# L-D5019-05-03.net
KiCad netlist of a schematic drawn in Altium Designer
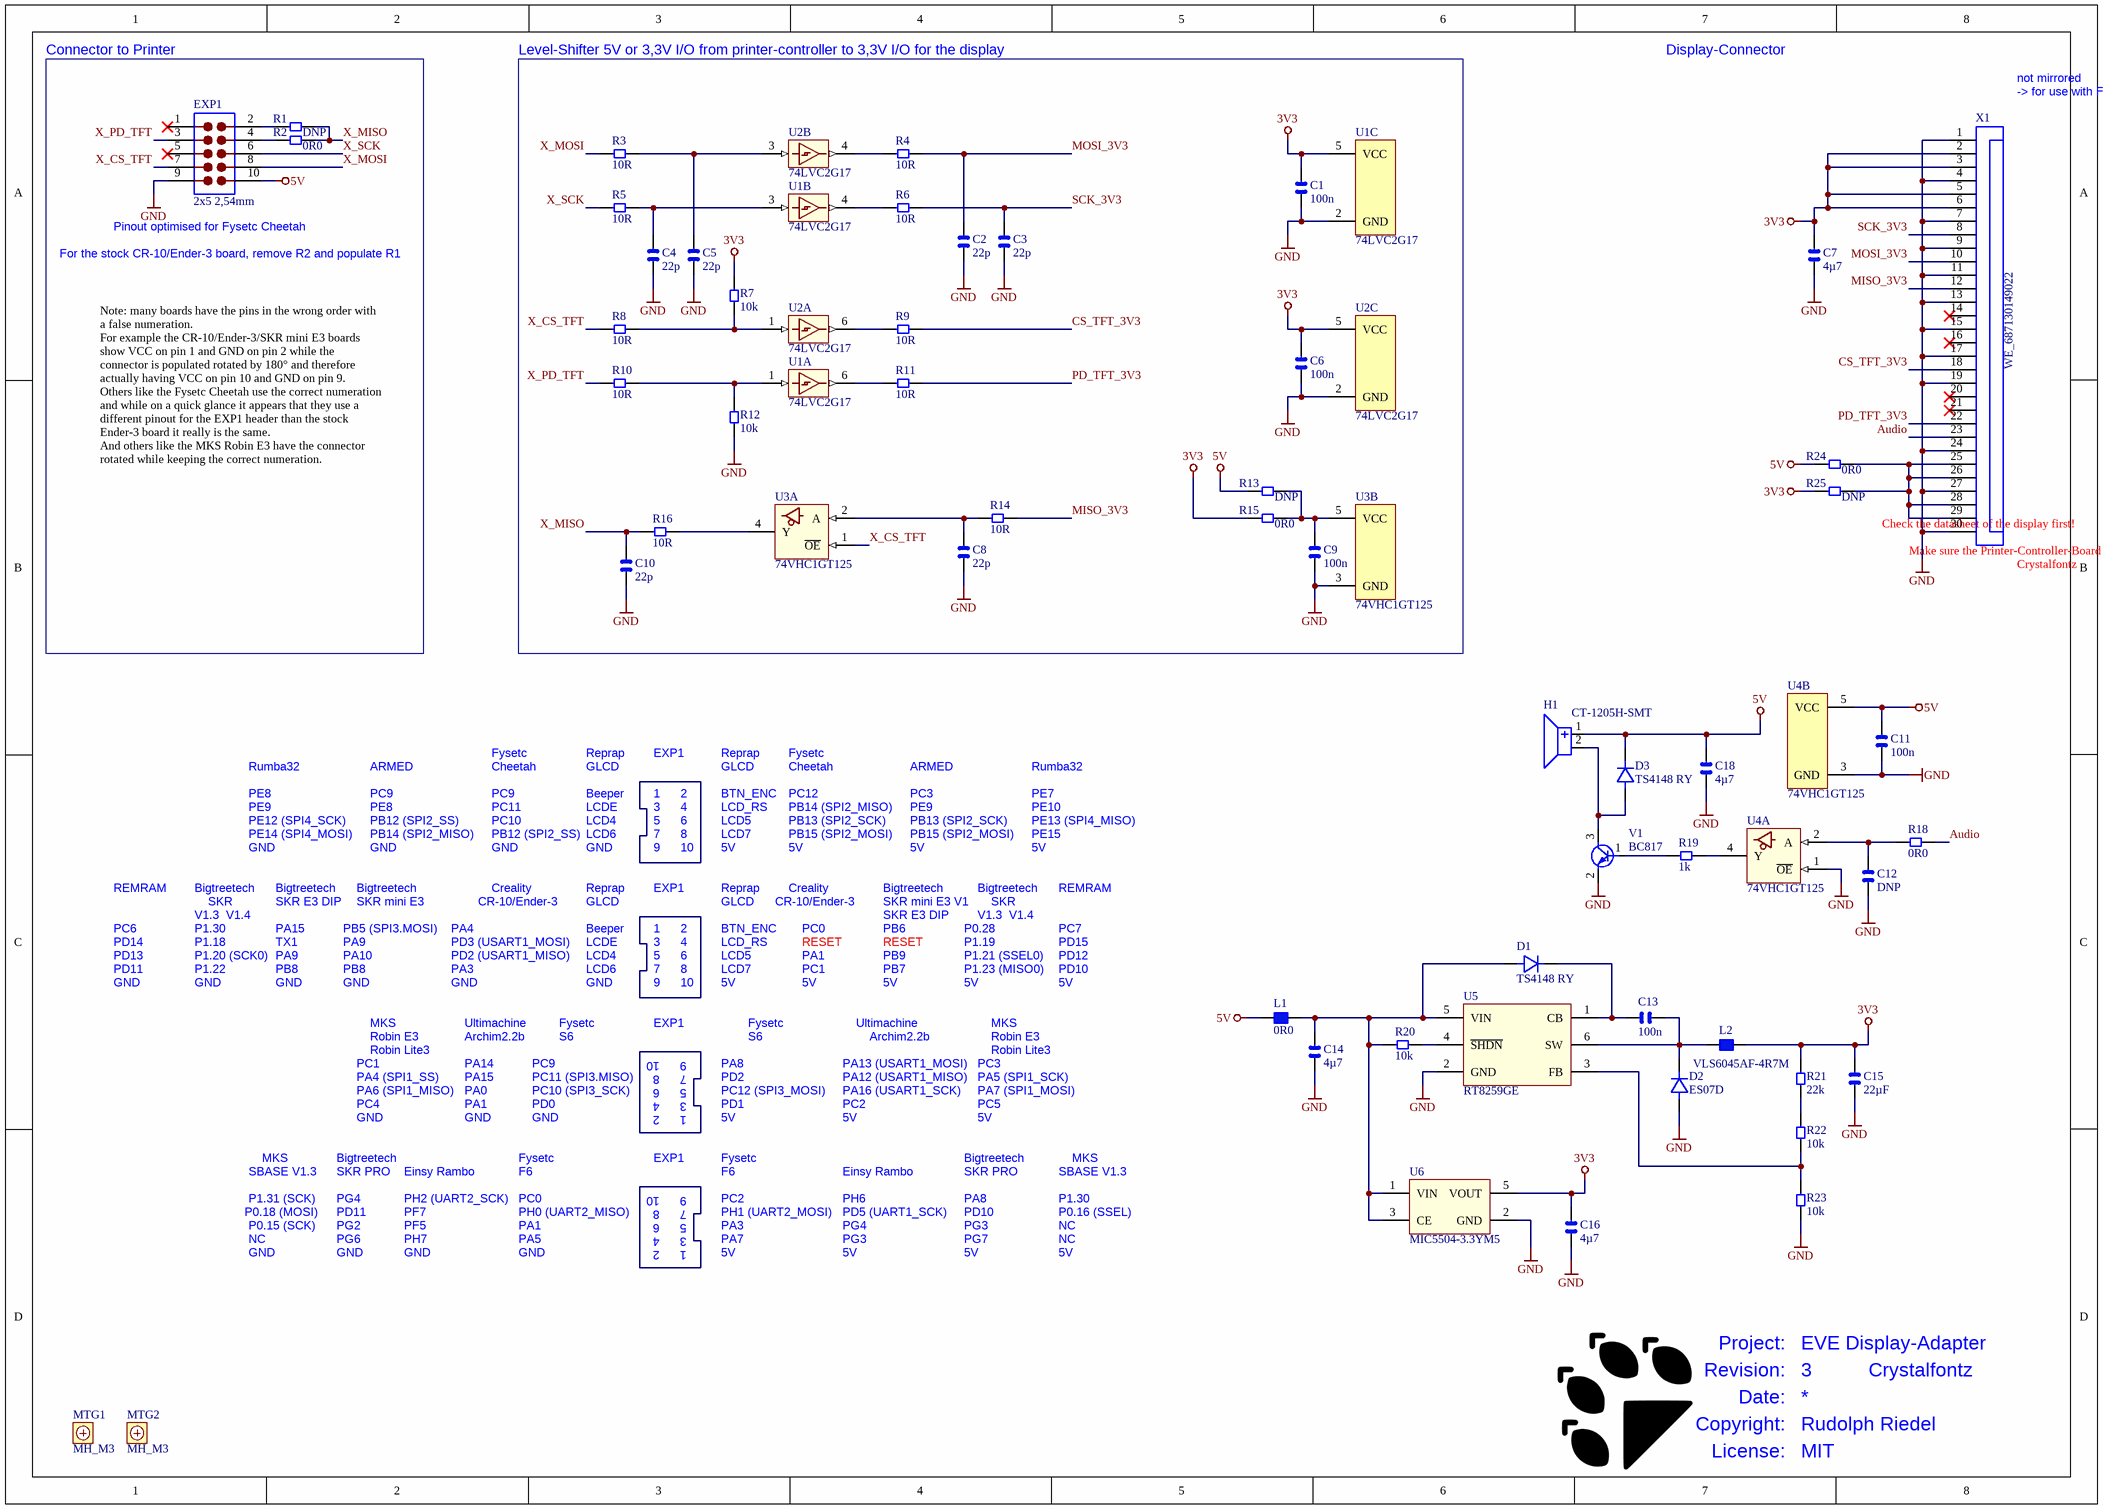
[diagram p0: L-D5019-05-03.SchDoc]

(export (version "E")
  (design (tool "Eeschema 10.0.6"))
  (components
    (comp (ref "C1")
      (value "100n")
      (footprint "CAPC2012X14L")
      (description "0805 Chip Capacitor")
      (fields (field (name "PART NUMBER") "CAPC_0805") (field (name "EDITOR") "rriedel"))
      (libsource (lib "HW-Labor_GF") (part "CAP_2_V2"))
    )
    (comp (ref "C2")
      (value "22p")
      (footprint "CAPC2012X14L")
      (description "0805 Chip Capacitor")
      (fields (field (name "PART NUMBER") "CAPC_0805") (field (name "EDITOR") "rriedel"))
      (libsource (lib "HW-Labor_GF") (part "CAP_2_V2"))
    )
    (comp (ref "C3")
      (value "22p")
      (footprint "CAPC2012X14L")
      (description "0805 Chip Capacitor")
      (fields (field (name "PART NUMBER") "CAPC_0805") (field (name "EDITOR") "rriedel"))
      (libsource (lib "HW-Labor_GF") (part "CAP_2_V2"))
    )
    (comp (ref "C4")
      (value "22p")
      (footprint "CAPC2012X14L")
      (description "0805 Chip Capacitor")
      (fields (field (name "PART NUMBER") "CAPC_0805") (field (name "EDITOR") "rriedel"))
      (libsource (lib "HW-Labor_GF") (part "CAP_2_V2"))
    )
    (comp (ref "C5")
      (value "22p")
      (footprint "CAPC2012X14L")
      (description "0805 Chip Capacitor")
      (fields (field (name "PART NUMBER") "CAPC_0805") (field (name "EDITOR") "rriedel"))
      (libsource (lib "HW-Labor_GF") (part "CAP_2_V2"))
    )
    (comp (ref "C6")
      (value "100n")
      (footprint "CAPC2012X14L")
      (description "0805 Chip Capacitor")
      (fields (field (name "PART NUMBER") "CAPC_0805") (field (name "EDITOR") "rriedel"))
      (libsource (lib "HW-Labor_GF") (part "CAP_2_V2"))
    )
    (comp (ref "C7")
      (value "4µ7")
      (footprint "CAPC2012X14L")
      (description "0805 Chip Capacitor")
      (fields (field (name "PART NUMBER") "CAPC_0805") (field (name "EDITOR") "rriedel"))
      (libsource (lib "HW-Labor_GF") (part "CAP_2_V2"))
    )
    (comp (ref "C8")
      (value "22p")
      (footprint "CAPC2012X14L")
      (description "0805 Chip Capacitor")
      (fields (field (name "PART NUMBER") "CAPC_0805") (field (name "EDITOR") "rriedel"))
      (libsource (lib "HW-Labor_GF") (part "CAP_2_V2"))
    )
    (comp (ref "C9")
      (value "100n")
      (footprint "CAPC2012X14L")
      (description "0805 Chip Capacitor")
      (fields (field (name "PART NUMBER") "CAPC_0805") (field (name "EDITOR") "rriedel"))
      (libsource (lib "HW-Labor_GF") (part "CAP_2_V2"))
    )
    (comp (ref "C10")
      (value "22p")
      (footprint "CAPC2012X14L")
      (description "0805 Chip Capacitor")
      (fields (field (name "PART NUMBER") "CAPC_0805") (field (name "EDITOR") "rriedel"))
      (libsource (lib "HW-Labor_GF") (part "CAP_2_V2"))
    )
    (comp (ref "C11")
      (value "100n")
      (footprint "CAPC2012X14L")
      (description "0805 Chip Capacitor")
      (fields (field (name "PART NUMBER") "CAPC_0805") (field (name "EDITOR") "rriedel"))
      (libsource (lib "HW-Labor_GF") (part "CAP_2_V2"))
    )
    (comp (ref "C12")
      (value "DNP")
      (footprint "CAPC2012X14L")
      (description "0805 Chip Capacitor")
      (fields (field (name "PART NUMBER") "CAPC_0805") (field (name "EDITOR") "rriedel"))
      (libsource (lib "HW-Labor_GF") (part "CAP_2_V2"))
    )
    (comp (ref "C13")
      (value "100n")
      (footprint "CAPC2012X14L")
      (description "0805 Chip Capacitor")
      (fields (field (name "PART NUMBER") "CAPC_0805") (field (name "EDITOR") "rriedel"))
      (libsource (lib "HW-Labor_GF") (part "CAP_2_V2"))
    )
    (comp (ref "C14")
      (value "4µ7")
      (footprint "CAPC2012X14L")
      (description "0805 Chip Capacitor")
      (fields (field (name "PART NUMBER") "CAPC_0805") (field (name "EDITOR") "rriedel"))
      (libsource (lib "HW-Labor_GF") (part "CAP_2_V2"))
    )
    (comp (ref "C15")
      (value "22µF")
      (footprint "CAPC3216X19N")
      (description "1206 Chip Capacitor")
      (fields (field (name "PART NUMBER") "CAPC_1206") (field (name "EDITOR") "rriedel"))
      (libsource (lib "HW-Labor_GF") (part "CAP_2_V2"))
    )
    (comp (ref "C16")
      (value "4µ7")
      (footprint "CAPC2012X14L")
      (description "0805 Chip Capacitor")
      (fields (field (name "PART NUMBER") "CAPC_0805") (field (name "ERSTELLER") "rriedel"))
      (libsource (lib "HW-Labor_GF") (part "CAP_2_V2"))
    )
    (comp (ref "C18")
      (value "4µ7")
      (footprint "CAPC2012X14L")
      (description "0805 Chip Capacitor")
      (fields (field (name "PART NUMBER") "CAPC_0805") (field (name "ERSTELLER") "rriedel"))
      (libsource (lib "HW-Labor_GF") (part "CAP_2_V2"))
    )
    (comp (ref "D1")
      (value "TS4148 RY")
      (footprint "DIOC2012X10N")
      (description "Small Signal Diode IF 0.3A, VR 75V, 0805")
      (fields
        (field (name "PART NUMBER") "TSC_TS4148 RY")
        (field (name "MANUFACTURER") "TSC")
        (field (name "EDITOR") "rriedel")
      )
      (libsource (lib "HW-Labor_GF") (part "Diode_A2_K1"))
    )
    (comp (ref "D2")
      (value "ES07D")
      (footprint "DIOM2818X11N")
      (description "Ultrafast Rectifier Surface Mount,  IF 0.5A, VR 100V, DO-219AB, AEC-Q101")
      (fields (field (name "MANUFACTURER") "Vishay") (field (name "EDITOR") "rriedel"))
      (libsource (lib "HW-Labor_GF") (part "Diode_A2_K1"))
    )
    (comp (ref "D3")
      (value "TS4148 RY")
      (footprint "DIOC2012X10N")
      (description "Small Signal Diode IF 0.3A, VR 75V, 0805")
      (fields
        (field (name "PART NUMBER") "TSC_TS4148 RY")
        (field (name "MANUFACTURER") "TSC")
        (field (name "EDITOR") "rriedel")
      )
      (libsource (lib "HW-Labor_GF") (part "Diode_A2_K1"))
    )
    (comp (ref "EXP1")
      (value "2x5 2,54mm")
      (footprint "PINH_2x5_2_54mm_shroud")
      (description "Pin-Header 2,54 mm 2x5pins, shrouded")
      (fields (field (name "PART NUMBER") "PINH_2x5_2_54") (field (name "EDITOR") "rriedel"))
      (libsource (lib "HW-Labor_GF") (part "CONM_2x5_V2"))
    )
    (comp (ref "H1")
      (value "CT-1205H-SMT")
      (footprint "CT-1205H-SMT")
      (description "Speaker, Magnetic, 47R, 60mA, 88dBA, SMT, 12.8 x 12.8 mm,  height 10 mm")
      (fields
        (field (name "MANUFACTURER") "CUI")
        (field (name "DISTRIBUTOR_1_PART_NUMBER") "102-1266-1-ND")
        (field (name "EDITOR") "rriedel")
      )
      (libsource (lib "HW-Labor_GF") (part "Speaker"))
    )
    (comp (ref "L1")
      (value "0R0")
      (footprint "INDC2012X10L")
      (description "0805 Chip Inductor")
      (fields (field (name "PART NUMBER") "INDC_0805") (field (name "EDITOR") "rriedel"))
      (libsource (lib "HW-Labor_GF") (part "IND_2_V1"))
    )
    (comp (ref "L2")
      (value "VLS6045AF-4R7M")
      (footprint "PowerInductor_6x6")
      (description "4,7µH, shielded, 4,7A, 26mR")
      (fields
        (field (name "MANUFACTURER") "TDK")
        (field (name "DISTRIBUTOR_1_PART_NUMBER") "445-180835-1-ND")
        (field (name "EDITOR") "rriedel")
      )
      (libsource (lib "HW-Labor_GF") (part "IND_2_V1"))
    )
    (comp (ref "MTG1")
      (value "MH_M3")
      (footprint "HOLE_3_2MM")
      (description "Mounting-Hole for M3 screws")
      (fields (field (name "EDITOR") "rriedel"))
      (libsource (lib "HW-Labor_GF") (part "MTG_V1"))
    )
    (comp (ref "MTG2")
      (value "MH_M3")
      (footprint "HOLE_3_2MM")
      (description "Mounting-Hole for M3 screws")
      (fields (field (name "EDITOR") "rriedel"))
      (libsource (lib "HW-Labor_GF") (part "MTG_V1"))
    )
    (comp (ref "R1")
      (value "DNP")
      (footprint "RESC2012X06L")
      (description "0805 Chip Resistor")
      (fields (field (name "PART NUMBER") "RESC_0805") (field (name "EDITOR") "rriedel"))
      (libsource (lib "HW-Labor_GF") (part "RES_2_V2"))
    )
    (comp (ref "R2")
      (value "0R0")
      (footprint "RESC2012X06L")
      (description "0805 Chip Resistor")
      (fields (field (name "PART NUMBER") "RESC_0805") (field (name "EDITOR") "rriedel"))
      (libsource (lib "HW-Labor_GF") (part "RES_2_V2"))
    )
    (comp (ref "R3")
      (value "10R")
      (footprint "RESC2012X06L")
      (description "0805 Chip Resistor")
      (fields (field (name "PART NUMBER") "RESC_0805") (field (name "EDITOR") "rriedel"))
      (libsource (lib "HW-Labor_GF") (part "RES_2_V2"))
    )
    (comp (ref "R4")
      (value "10R")
      (footprint "RESC2012X06L")
      (description "0805 Chip Resistor")
      (fields (field (name "PART NUMBER") "RESC_0805") (field (name "EDITOR") "rriedel"))
      (libsource (lib "HW-Labor_GF") (part "RES_2_V2"))
    )
    (comp (ref "R5")
      (value "10R")
      (footprint "RESC2012X06L")
      (description "0805 Chip Resistor")
      (fields (field (name "PART NUMBER") "RESC_0805") (field (name "EDITOR") "rriedel"))
      (libsource (lib "HW-Labor_GF") (part "RES_2_V2"))
    )
    (comp (ref "R6")
      (value "10R")
      (footprint "RESC2012X06L")
      (description "0805 Chip Resistor")
      (fields (field (name "PART NUMBER") "RESC_0805") (field (name "EDITOR") "rriedel"))
      (libsource (lib "HW-Labor_GF") (part "RES_2_V2"))
    )
    (comp (ref "R7")
      (value "10k")
      (footprint "RESC2012X06L")
      (description "0805 Chip Resistor")
      (fields (field (name "PART NUMBER") "RESC_0805") (field (name "EDITOR") "rriedel"))
      (libsource (lib "HW-Labor_GF") (part "RES_2_V2"))
    )
    (comp (ref "R8")
      (value "10R")
      (footprint "RESC2012X06L")
      (description "0805 Chip Resistor")
      (fields (field (name "PART NUMBER") "RESC_0805") (field (name "EDITOR") "rriedel"))
      (libsource (lib "HW-Labor_GF") (part "RES_2_V2"))
    )
    (comp (ref "R9")
      (value "10R")
      (footprint "RESC2012X06L")
      (description "0805 Chip Resistor")
      (fields (field (name "PART NUMBER") "RESC_0805") (field (name "EDITOR") "rriedel"))
      (libsource (lib "HW-Labor_GF") (part "RES_2_V2"))
    )
    (comp (ref "R10")
      (value "10R")
      (footprint "RESC2012X06L")
      (description "0805 Chip Resistor")
      (fields (field (name "PART NUMBER") "RESC_0805") (field (name "EDITOR") "rriedel"))
      (libsource (lib "HW-Labor_GF") (part "RES_2_V2"))
    )
    (comp (ref "R11")
      (value "10R")
      (footprint "RESC2012X06L")
      (description "0805 Chip Resistor")
      (fields (field (name "PART NUMBER") "RESC_0805") (field (name "EDITOR") "rriedel"))
      (libsource (lib "HW-Labor_GF") (part "RES_2_V2"))
    )
    (comp (ref "R12")
      (value "10k")
      (footprint "RESC2012X06L")
      (description "0805 Chip Resistor")
      (fields (field (name "PART NUMBER") "RESC_0805") (field (name "EDITOR") "rriedel"))
      (libsource (lib "HW-Labor_GF") (part "RES_2_V2"))
    )
    (comp (ref "R13")
      (value "DNP")
      (footprint "RESC2012X06L")
      (description "0805 Chip Resistor")
      (fields (field (name "PART NUMBER") "RESC_0805") (field (name "EDITOR") "rriedel"))
      (libsource (lib "HW-Labor_GF") (part "RES_2_V2"))
    )
    (comp (ref "R14")
      (value "10R")
      (footprint "RESC2012X06L")
      (description "0805 Chip Resistor")
      (fields (field (name "PART NUMBER") "RESC_0805") (field (name "EDITOR") "rriedel"))
      (libsource (lib "HW-Labor_GF") (part "RES_2_V2"))
    )
    (comp (ref "R15")
      (value "0R0")
      (footprint "RESC2012X06L")
      (description "0805 Chip Resistor")
      (fields (field (name "PART NUMBER") "RESC_0805") (field (name "EDITOR") "rriedel"))
      (libsource (lib "HW-Labor_GF") (part "RES_2_V2"))
    )
    (comp (ref "R16")
      (value "10R")
      (footprint "RESC2012X06L")
      (description "0805 Chip Resistor")
      (fields (field (name "PART NUMBER") "RESC_0805") (field (name "EDITOR") "rriedel"))
      (libsource (lib "HW-Labor_GF") (part "RES_2_V2"))
    )
    (comp (ref "R18")
      (value "0R0")
      (footprint "RESC2012X06L")
      (description "0805 Chip Resistor")
      (fields (field (name "PART NUMBER") "RESC_0805") (field (name "EDITOR") "rriedel"))
      (libsource (lib "HW-Labor_GF") (part "RES_2_V2"))
    )
    (comp (ref "R19")
      (value "1k")
      (footprint "RESC2012X06L")
      (description "0805 Chip Resistor")
      (fields (field (name "PART NUMBER") "RESC_0805") (field (name "EDITOR") "rriedel"))
      (libsource (lib "HW-Labor_GF") (part "RES_2_V2"))
    )
    (comp (ref "R20")
      (value "10k")
      (footprint "RESC2012X06L")
      (description "0805 Chip Resistor")
      (fields (field (name "PART NUMBER") "RESC_0805") (field (name "EDITOR") "rriedel"))
      (libsource (lib "HW-Labor_GF") (part "RES_2_V2"))
    )
    (comp (ref "R21")
      (value "22k")
      (footprint "RESC2012X06L")
      (description "0805 Chip Resistor")
      (fields (field (name "PART NUMBER") "RESC_0805") (field (name "EDITOR") "rriedel"))
      (libsource (lib "HW-Labor_GF") (part "RES_2_V2"))
    )
    (comp (ref "R22")
      (value "10k")
      (footprint "RESC2012X06L")
      (description "0805 Chip Resistor")
      (fields (field (name "PART NUMBER") "RESC_0805") (field (name "EDITOR") "rriedel"))
      (libsource (lib "HW-Labor_GF") (part "RES_2_V2"))
    )
    (comp (ref "R23")
      (value "10k")
      (footprint "RESC2012X06L")
      (description "0805 Chip Resistor")
      (fields (field (name "PART NUMBER") "RESC_0805") (field (name "EDITOR") "rriedel"))
      (libsource (lib "HW-Labor_GF") (part "RES_2_V2"))
    )
    (comp (ref "R24")
      (value "0R0")
      (footprint "RESC2012X06L")
      (description "0805 Chip Resistor")
      (fields (field (name "PART NUMBER") "RESC_0805") (field (name "EDITOR") "rriedel"))
      (libsource (lib "HW-Labor_GF") (part "RES_2_V2"))
    )
    (comp (ref "R25")
      (value "DNP")
      (footprint "RESC2012X06L")
      (description "0805 Chip Resistor")
      (fields (field (name "PART NUMBER") "RESC_0805") (field (name "EDITOR") "rriedel"))
      (libsource (lib "HW-Labor_GF") (part "RES_2_V2"))
    )
    (comp (ref "U1")
      (value "74LVC2G17")
      (footprint "SOT95P280X110-6N")
      (description "Dual Schmitt-Trigger Buffer with 5.5V tolerant inputs")
      (fields
        (field (name "MANUFACTURER") "TI")
        (field (name "DISTRIBUTOR_1_PART_NUMBER") "296-SN74LVC2G17DBVRCT-ND‎")
        (field (name "EDITOR") "rriedel")
      )
      (libsource (lib "HW-Labor_GF") (part "74LVC2G17"))
    )
    (comp (ref "U2")
      (value "74LVC2G17")
      (footprint "SOT95P280X110-6N")
      (description "Dual Schmitt-Trigger Buffer with 5.5V tolerant inputs")
      (fields
        (field (name "MANUFACTURER") "TI")
        (field (name "DISTRIBUTOR_1_PART_NUMBER") "296-SN74LVC2G17DBVRCT-ND‎")
        (field (name "EDITOR") "rriedel")
      )
      (libsource (lib "HW-Labor_GF") (part "74LVC2G17"))
    )
    (comp (ref "U3")
      (value "74VHC1GT125")
      (footprint "SOT95P280X110-5N")
      (description "1x Buffer with OE; 3-state,Level Shifter 3,3V to 5V and 5V to 3.3V")
      (fields
        (field (name "MANUFACTURER") "ON Semiconductor")
        (field (name "DISTRIBUTOR_1_PART_NUMBER") "1703291")
        (field (name "EDITOR") "rriedel")
      )
      (libsource (lib "HW-Labor_GF") (part "74LVC1G125G"))
    )
    (comp (ref "U4")
      (value "74VHC1GT125")
      (footprint "SOT95P280X110-5N")
      (description "1x Buffer with OE; 3-state,Level Shifter 3,3V to 5V and 5V to 3.3V")
      (fields
        (field (name "MANUFACTURER") "ON Semiconductor")
        (field (name "DISTRIBUTOR_1_PART_NUMBER") "1703291")
        (field (name "EDITOR") "rriedel")
      )
      (libsource (lib "HW-Labor_GF") (part "74LVC1G125G"))
    )
    (comp (ref "U5")
      (value "RT8259GE")
      (footprint "SOT95P280X110-6N")
      (description "Step-Down DC/DC Regulator, 24V, 1.2A, 1,4MHz")
      (fields
        (field (name "MANUFACTURER") "Richtek")
        (field (name "DISTRIBUTOR_1_PART_NUMBER") "1028-1497-1-ND")
        (field (name "EDITOR") "rriedel")
      )
      (libsource (lib "HW-Labor_GF") (part "StepDown_SOT23-6"))
    )
    (comp (ref "U6")
      (value "MIC5504-3.3YM5")
      (footprint "SOT95P280X110-5N")
      (description "300 mA LDO,  Vin=2,5V…5,5V, Vout= 3,3V, -40°C..125°C")
      (fields
        (field (name "MANUFACTURER") "Microchip")
        (field (name "DISTRIBUTOR_1_PART_NUMBER") "2510377")
        (field (name "EDITOR") "rriedel")
      )
      (libsource (lib "HW-Labor_GF") (part "LDO_SOT23-5"))
    )
    (comp (ref "V1")
      (value "BC817")
      (footprint "SOT95P280X110-3N")
      (description "NPN Transistor SOT23, 1=B, 2=C, 3=E")
      (fields (field (name "EDITOR") "rriedel"))
      (libsource (lib "HW-Labor_GF") (part "NPN_B1_C2_E3"))
    )
    (comp (ref "X1")
      (value "WE_687130149022")
      (footprint "WE_687130149022")
      (description "30pin WR-FPC 0.50 mm SMT ZIF Horizontal - Bottom Contact")
      (fields
        (field (name "MANUFACTURER") "Wuerth")
        (field (name "DISTRIBUTOR_1_PART_NUMBER") "732-6007-1-ND")
        (field (name "EDITOR") "rriedel")
      )
      (libsource (lib "HW-Labor_GF") (part "FPC_30"))
    )
  )
  (nets
    (net (code "1") (name "/Audio") (class "Default")
      (node (ref "R18") (pin "2") (pinfunction "2_2") (pintype "passive"))
      (node (ref "X1") (pin "23") (pinfunction "23_23") (pintype "passive"))
    )
    (net (code "2") (name "/CS_TFT_3V3") (class "Default")
      (node (ref "R9") (pin "2") (pinfunction "2_2") (pintype "passive"))
      (node (ref "X1") (pin "18") (pinfunction "18_18") (pintype "passive"))
    )
    (net (code "3") (name "/MISO_3V3") (class "Default")
      (node (ref "R14") (pin "2") (pinfunction "2_2") (pintype "passive"))
      (node (ref "X1") (pin "12") (pinfunction "12_12") (pintype "passive"))
    )
    (net (code "4") (name "/MOSI_3V3") (class "Default")
      (node (ref "C2") (pin "2") (pinfunction "2_2") (pintype "passive"))
      (node (ref "R4") (pin "2") (pinfunction "2_2") (pintype "passive"))
      (node (ref "X1") (pin "10") (pinfunction "10_10") (pintype "passive"))
    )
    (net (code "5") (name "/PD_TFT_3V3") (class "Default")
      (node (ref "R11") (pin "2") (pinfunction "2_2") (pintype "passive"))
      (node (ref "X1") (pin "22") (pinfunction "22_22") (pintype "passive"))
    )
    (net (code "6") (name "/SCK_3V3") (class "Default")
      (node (ref "C3") (pin "2") (pinfunction "2_2") (pintype "passive"))
      (node (ref "R6") (pin "2") (pinfunction "2_2") (pintype "passive"))
      (node (ref "X1") (pin "8") (pinfunction "8_8") (pintype "passive"))
    )
    (net (code "7") (name "/X_CS_TFT") (class "Default")
      (node (ref "EXP1") (pin "7") (pinfunction "7_7") (pintype "passive"))
      (node (ref "R8") (pin "1") (pinfunction "1_1") (pintype "passive"))
      (node (ref "U3") (pin "1") (pinfunction "~{OE}_1") (pintype "input"))
    )
    (net (code "8") (name "/X_MISO") (class "Default")
      (node (ref "C10") (pin "2") (pinfunction "2_2") (pintype "passive"))
      (node (ref "R1") (pin "2") (pinfunction "2_2") (pintype "passive"))
      (node (ref "R16") (pin "1") (pinfunction "1_1") (pintype "passive"))
      (node (ref "R2") (pin "2") (pinfunction "2_2") (pintype "passive"))
    )
    (net (code "9") (name "/X_MOSI") (class "Default")
      (node (ref "EXP1") (pin "8") (pinfunction "8_8") (pintype "passive"))
      (node (ref "R3") (pin "1") (pinfunction "1_1") (pintype "passive"))
    )
    (net (code "10") (name "/X_PD_TFT") (class "Default")
      (node (ref "EXP1") (pin "3") (pinfunction "3_3") (pintype "passive"))
      (node (ref "R10") (pin "1") (pinfunction "1_1") (pintype "passive"))
    )
    (net (code "11") (name "/X_SCK") (class "Default")
      (node (ref "EXP1") (pin "6") (pinfunction "6_6") (pintype "passive"))
      (node (ref "R5") (pin "1") (pinfunction "1_1") (pintype "passive"))
    )
    (net (code "12") (name "3V3") (class "Default")
      (node (ref "C1") (pin "2") (pinfunction "2_2") (pintype "passive"))
      (node (ref "C15") (pin "2") (pinfunction "2_2") (pintype "passive"))
      (node (ref "C16") (pin "2") (pinfunction "2_2") (pintype "passive"))
      (node (ref "C6") (pin "2") (pinfunction "2_2") (pintype "passive"))
      (node (ref "C7") (pin "2") (pinfunction "2_2") (pintype "passive"))
      (node (ref "L2") (pin "2") (pinfunction "2_2") (pintype "passive"))
      (node (ref "R15") (pin "1") (pinfunction "1_1") (pintype "passive"))
      (node (ref "R21") (pin "2") (pinfunction "2_2") (pintype "passive"))
      (node (ref "R25") (pin "1") (pinfunction "1_1") (pintype "passive"))
      (node (ref "R7") (pin "2") (pinfunction "2_2") (pintype "passive"))
      (node (ref "U1") (pin "5") (pinfunction "VCC_5") (pintype "power_in"))
      (node (ref "U2") (pin "5") (pinfunction "VCC_5") (pintype "power_in"))
      (node (ref "U6") (pin "5") (pinfunction "VOUT_5") (pintype "passive"))
      (node (ref "X1") (pin "2") (pinfunction "2_2") (pintype "passive"))
      (node (ref "X1") (pin "3") (pinfunction "3_3") (pintype "passive"))
      (node (ref "X1") (pin "5") (pinfunction "5_5") (pintype "passive"))
      (node (ref "X1") (pin "6") (pinfunction "6_6") (pintype "passive"))
    )
    (net (code "13") (name "5V") (class "Default")
      (node (ref "C11") (pin "2") (pinfunction "2_2") (pintype "passive"))
      (node (ref "C18") (pin "2") (pinfunction "2_2") (pintype "passive"))
      (node (ref "D3") (pin "1") (pinfunction "1_1") (pintype "passive"))
      (node (ref "EXP1") (pin "10") (pinfunction "10_10") (pintype "passive"))
      (node (ref "H1") (pin "1") (pinfunction "1_1") (pintype "passive"))
      (node (ref "L1") (pin "1") (pinfunction "1_1") (pintype "passive"))
      (node (ref "R13") (pin "1") (pinfunction "1_1") (pintype "passive"))
      (node (ref "R24") (pin "1") (pinfunction "1_1") (pintype "passive"))
      (node (ref "U4") (pin "5") (pinfunction "VCC_5") (pintype "passive"))
    )
    (net (code "14") (name "GND") (class "Default")
      (node (ref "C1") (pin "1") (pinfunction "1_1") (pintype "passive"))
      (node (ref "C10") (pin "1") (pinfunction "1_1") (pintype "passive"))
      (node (ref "C11") (pin "1") (pinfunction "1_1") (pintype "passive"))
      (node (ref "C12") (pin "1") (pinfunction "1_1") (pintype "passive"))
      (node (ref "C14") (pin "1") (pinfunction "1_1") (pintype "passive"))
      (node (ref "C15") (pin "1") (pinfunction "1_1") (pintype "passive"))
      (node (ref "C16") (pin "1") (pinfunction "1_1") (pintype "passive"))
      (node (ref "C18") (pin "1") (pinfunction "1_1") (pintype "passive"))
      (node (ref "C2") (pin "1") (pinfunction "1_1") (pintype "passive"))
      (node (ref "C3") (pin "1") (pinfunction "1_1") (pintype "passive"))
      (node (ref "C4") (pin "1") (pinfunction "1_1") (pintype "passive"))
      (node (ref "C5") (pin "1") (pinfunction "1_1") (pintype "passive"))
      (node (ref "C6") (pin "1") (pinfunction "1_1") (pintype "passive"))
      (node (ref "C7") (pin "1") (pinfunction "1_1") (pintype "passive"))
      (node (ref "C8") (pin "1") (pinfunction "1_1") (pintype "passive"))
      (node (ref "C9") (pin "1") (pinfunction "1_1") (pintype "passive"))
      (node (ref "D2") (pin "2") (pinfunction "2_2") (pintype "passive"))
      (node (ref "EXP1") (pin "9") (pinfunction "9_9") (pintype "passive"))
      (node (ref "R12") (pin "1") (pinfunction "1_1") (pintype "passive"))
      (node (ref "R23") (pin "1") (pinfunction "1_1") (pintype "passive"))
      (node (ref "U1") (pin "2") (pinfunction "GND_2") (pintype "power_in"))
      (node (ref "U2") (pin "2") (pinfunction "GND_2") (pintype "power_in"))
      (node (ref "U3") (pin "3") (pinfunction "GND_3") (pintype "passive"))
      (node (ref "U4") (pin "1") (pinfunction "~{OE}_1") (pintype "input"))
      (node (ref "U4") (pin "3") (pinfunction "GND_3") (pintype "passive"))
      (node (ref "U5") (pin "2") (pinfunction "GND_2") (pintype "power_in"))
      (node (ref "U6") (pin "2") (pinfunction "GND_2") (pintype "passive"))
      (node (ref "V1") (pin "2") (pinfunction "2_2") (pintype "passive"))
      (node (ref "X1") (pin "1") (pinfunction "1_1") (pintype "passive"))
      (node (ref "X1") (pin "11") (pinfunction "11_11") (pintype "passive"))
      (node (ref "X1") (pin "13") (pinfunction "13_13") (pintype "passive"))
      (node (ref "X1") (pin "15") (pinfunction "15_15") (pintype "passive"))
      (node (ref "X1") (pin "17") (pinfunction "17_17") (pintype "passive"))
      (node (ref "X1") (pin "19") (pinfunction "19_19") (pintype "passive"))
      (node (ref "X1") (pin "24") (pinfunction "24_24") (pintype "passive"))
      (node (ref "X1") (pin "27") (pinfunction "27_27") (pintype "passive"))
      (node (ref "X1") (pin "30") (pinfunction "30_30") (pintype "passive"))
      (node (ref "X1") (pin "4") (pinfunction "4_4") (pintype "passive"))
      (node (ref "X1") (pin "7") (pinfunction "7_7") (pintype "passive"))
      (node (ref "X1") (pin "9") (pinfunction "9_9") (pintype "passive"))
    )
    (net (code "15") (name "Net-(D3-Pad2)") (class "Default")
      (node (ref "D3") (pin "2") (pinfunction "2_2") (pintype "passive"))
      (node (ref "H1") (pin "2") (pinfunction "2_2") (pintype "passive"))
      (node (ref "V1") (pin "3") (pinfunction "3_3") (pintype "passive"))
    )
    (net (code "16") (name "Net-(EXP1-Pad2)") (class "Default")
      (node (ref "EXP1") (pin "2") (pinfunction "2_2") (pintype "passive"))
      (node (ref "R1") (pin "1") (pinfunction "1_1") (pintype "passive"))
    )
    (net (code "17") (name "Net-(EXP1-Pad4)") (class "Default")
      (node (ref "EXP1") (pin "4") (pinfunction "4_4") (pintype "passive"))
      (node (ref "R2") (pin "1") (pinfunction "1_1") (pintype "passive"))
    )
    (net (code "18") (name "Net-(R19-Pad2)") (class "Default")
      (node (ref "R19") (pin "2") (pinfunction "2_2") (pintype "passive"))
      (node (ref "V1") (pin "1") (pinfunction "1_1") (pintype "passive"))
    )
    (net (code "19") (name "Net-(R21-Pad1)") (class "Default")
      (node (ref "R21") (pin "1") (pinfunction "1_1") (pintype "passive"))
      (node (ref "R22") (pin "2") (pinfunction "2_2") (pintype "passive"))
    )
    (net (code "20") (name "Net-(R24-Pad2)") (class "Default")
      (node (ref "R24") (pin "2") (pinfunction "2_2") (pintype "passive"))
      (node (ref "R25") (pin "2") (pinfunction "2_2") (pintype "passive"))
      (node (ref "X1") (pin "25") (pinfunction "25_25") (pintype "passive"))
      (node (ref "X1") (pin "26") (pinfunction "26_26") (pintype "passive"))
      (node (ref "X1") (pin "28") (pinfunction "28_28") (pintype "passive"))
      (node (ref "X1") (pin "29") (pinfunction "29_29") (pintype "passive"))
    )
    (net (code "21") (name "Net-(U1A-1A)") (class "Default")
      (node (ref "R10") (pin "2") (pinfunction "2_2") (pintype "passive"))
      (node (ref "R12") (pin "2") (pinfunction "2_2") (pintype "passive"))
      (node (ref "U1") (pin "1") (pinfunction "1A_1") (pintype "input"))
    )
    (net (code "22") (name "Net-(U1A-1Y)") (class "Default")
      (node (ref "R11") (pin "1") (pinfunction "1_1") (pintype "passive"))
      (node (ref "U1") (pin "6") (pinfunction "1Y_6") (pintype "output"))
    )
    (net (code "23") (name "Net-(U1B-2A)") (class "Default")
      (node (ref "C4") (pin "2") (pinfunction "2_2") (pintype "passive"))
      (node (ref "R5") (pin "2") (pinfunction "2_2") (pintype "passive"))
      (node (ref "U1") (pin "3") (pinfunction "2A_3") (pintype "input"))
    )
    (net (code "24") (name "Net-(U1B-2Y)") (class "Default")
      (node (ref "R6") (pin "1") (pinfunction "1_1") (pintype "passive"))
      (node (ref "U1") (pin "4") (pinfunction "2Y_4") (pintype "output"))
    )
    (net (code "25") (name "Net-(U2A-1A)") (class "Default")
      (node (ref "R7") (pin "1") (pinfunction "1_1") (pintype "passive"))
      (node (ref "R8") (pin "2") (pinfunction "2_2") (pintype "passive"))
      (node (ref "U2") (pin "1") (pinfunction "1A_1") (pintype "input"))
    )
    (net (code "26") (name "Net-(U2A-1Y)") (class "Default")
      (node (ref "R9") (pin "1") (pinfunction "1_1") (pintype "passive"))
      (node (ref "U2") (pin "6") (pinfunction "1Y_6") (pintype "output"))
    )
    (net (code "27") (name "Net-(U2B-2A)") (class "Default")
      (node (ref "C5") (pin "2") (pinfunction "2_2") (pintype "passive"))
      (node (ref "R3") (pin "2") (pinfunction "2_2") (pintype "passive"))
      (node (ref "U2") (pin "3") (pinfunction "2A_3") (pintype "input"))
    )
    (net (code "28") (name "Net-(U2B-2Y)") (class "Default")
      (node (ref "R4") (pin "1") (pinfunction "1_1") (pintype "passive"))
      (node (ref "U2") (pin "4") (pinfunction "2Y_4") (pintype "output"))
    )
    (net (code "29") (name "Net-(U3A-A)") (class "Default")
      (node (ref "C8") (pin "2") (pinfunction "2_2") (pintype "passive"))
      (node (ref "R14") (pin "1") (pinfunction "1_1") (pintype "passive"))
      (node (ref "U3") (pin "2") (pinfunction "A_2") (pintype "input"))
    )
    (net (code "30") (name "Net-(U3A-Y)") (class "Default")
      (node (ref "R16") (pin "2") (pinfunction "2_2") (pintype "passive"))
      (node (ref "U3") (pin "4") (pinfunction "Y_4") (pintype "tri_state"))
    )
    (net (code "31") (name "Net-(U3B-VCC)") (class "Default")
      (node (ref "C9") (pin "2") (pinfunction "2_2") (pintype "passive"))
      (node (ref "R13") (pin "2") (pinfunction "2_2") (pintype "passive"))
      (node (ref "R15") (pin "2") (pinfunction "2_2") (pintype "passive"))
      (node (ref "U3") (pin "5") (pinfunction "VCC_5") (pintype "passive"))
    )
    (net (code "32") (name "Net-(U4A-A)") (class "Default")
      (node (ref "C12") (pin "2") (pinfunction "2_2") (pintype "passive"))
      (node (ref "R18") (pin "1") (pinfunction "1_1") (pintype "passive"))
      (node (ref "U4") (pin "2") (pinfunction "A_2") (pintype "input"))
    )
    (net (code "33") (name "Net-(U4A-Y)") (class "Default")
      (node (ref "R19") (pin "1") (pinfunction "1_1") (pintype "passive"))
      (node (ref "U4") (pin "4") (pinfunction "Y_4") (pintype "tri_state"))
    )
    (net (code "34") (name "Net-(U5-CB)") (class "Default")
      (node (ref "C13") (pin "1") (pinfunction "1_1") (pintype "passive"))
      (node (ref "D1") (pin "1") (pinfunction "1_1") (pintype "passive"))
      (node (ref "U5") (pin "1") (pinfunction "CB_1") (pintype "passive"))
    )
    (net (code "35") (name "Net-(U5-FB)") (class "Default")
      (node (ref "R22") (pin "1") (pinfunction "1_1") (pintype "passive"))
      (node (ref "R23") (pin "2") (pinfunction "2_2") (pintype "passive"))
      (node (ref "U5") (pin "3") (pinfunction "FB_3") (pintype "passive"))
    )
    (net (code "36") (name "Net-(U5-SW)") (class "Default")
      (node (ref "C13") (pin "2") (pinfunction "2_2") (pintype "passive"))
      (node (ref "D2") (pin "1") (pinfunction "1_1") (pintype "passive"))
      (node (ref "L2") (pin "1") (pinfunction "1_1") (pintype "passive"))
      (node (ref "U5") (pin "6") (pinfunction "SW_6") (pintype "passive"))
    )
    (net (code "37") (name "Net-(U5-VIN)") (class "Default")
      (node (ref "C14") (pin "2") (pinfunction "2_2") (pintype "passive"))
      (node (ref "D1") (pin "2") (pinfunction "2_2") (pintype "passive"))
      (node (ref "L1") (pin "2") (pinfunction "2_2") (pintype "passive"))
      (node (ref "R20") (pin "1") (pinfunction "1_1") (pintype "passive"))
      (node (ref "U5") (pin "5") (pinfunction "VIN_5") (pintype "power_in"))
      (node (ref "U6") (pin "1") (pinfunction "VIN_1") (pintype "passive"))
      (node (ref "U6") (pin "3") (pinfunction "CE_3") (pintype "passive"))
    )
    (net (code "38") (name "Net-(U5-~{SHDN})") (class "Default")
      (node (ref "R20") (pin "2") (pinfunction "2_2") (pintype "passive"))
      (node (ref "U5") (pin "4") (pinfunction "~{SHDN}_4") (pintype "passive"))
    )
    (net (code "39") (name "unconnected-(EXP1-Pad1)") (class "Default")
      (node (ref "EXP1") (pin "1") (pinfunction "1_1") (pintype "passive+no_connect"))
    )
    (net (code "40") (name "unconnected-(EXP1-Pad5)") (class "Default")
      (node (ref "EXP1") (pin "5") (pinfunction "5_5") (pintype "passive+no_connect"))
    )
    (net (code "41") (name "unconnected-(X1-Pad14)") (class "Default")
      (node (ref "X1") (pin "14") (pinfunction "14_14") (pintype "passive+no_connect"))
    )
    (net (code "42") (name "unconnected-(X1-Pad16)") (class "Default")
      (node (ref "X1") (pin "16") (pinfunction "16_16") (pintype "passive+no_connect"))
    )
    (net (code "43") (name "unconnected-(X1-Pad20)") (class "Default")
      (node (ref "X1") (pin "20") (pinfunction "20_20") (pintype "passive+no_connect"))
    )
    (net (code "44") (name "unconnected-(X1-Pad21)") (class "Default")
      (node (ref "X1") (pin "21") (pinfunction "21_21") (pintype "passive+no_connect"))
    )
  )
)
